# Cing_MainBoard.net
KiCad netlist of a schematic drawn in EAGLE
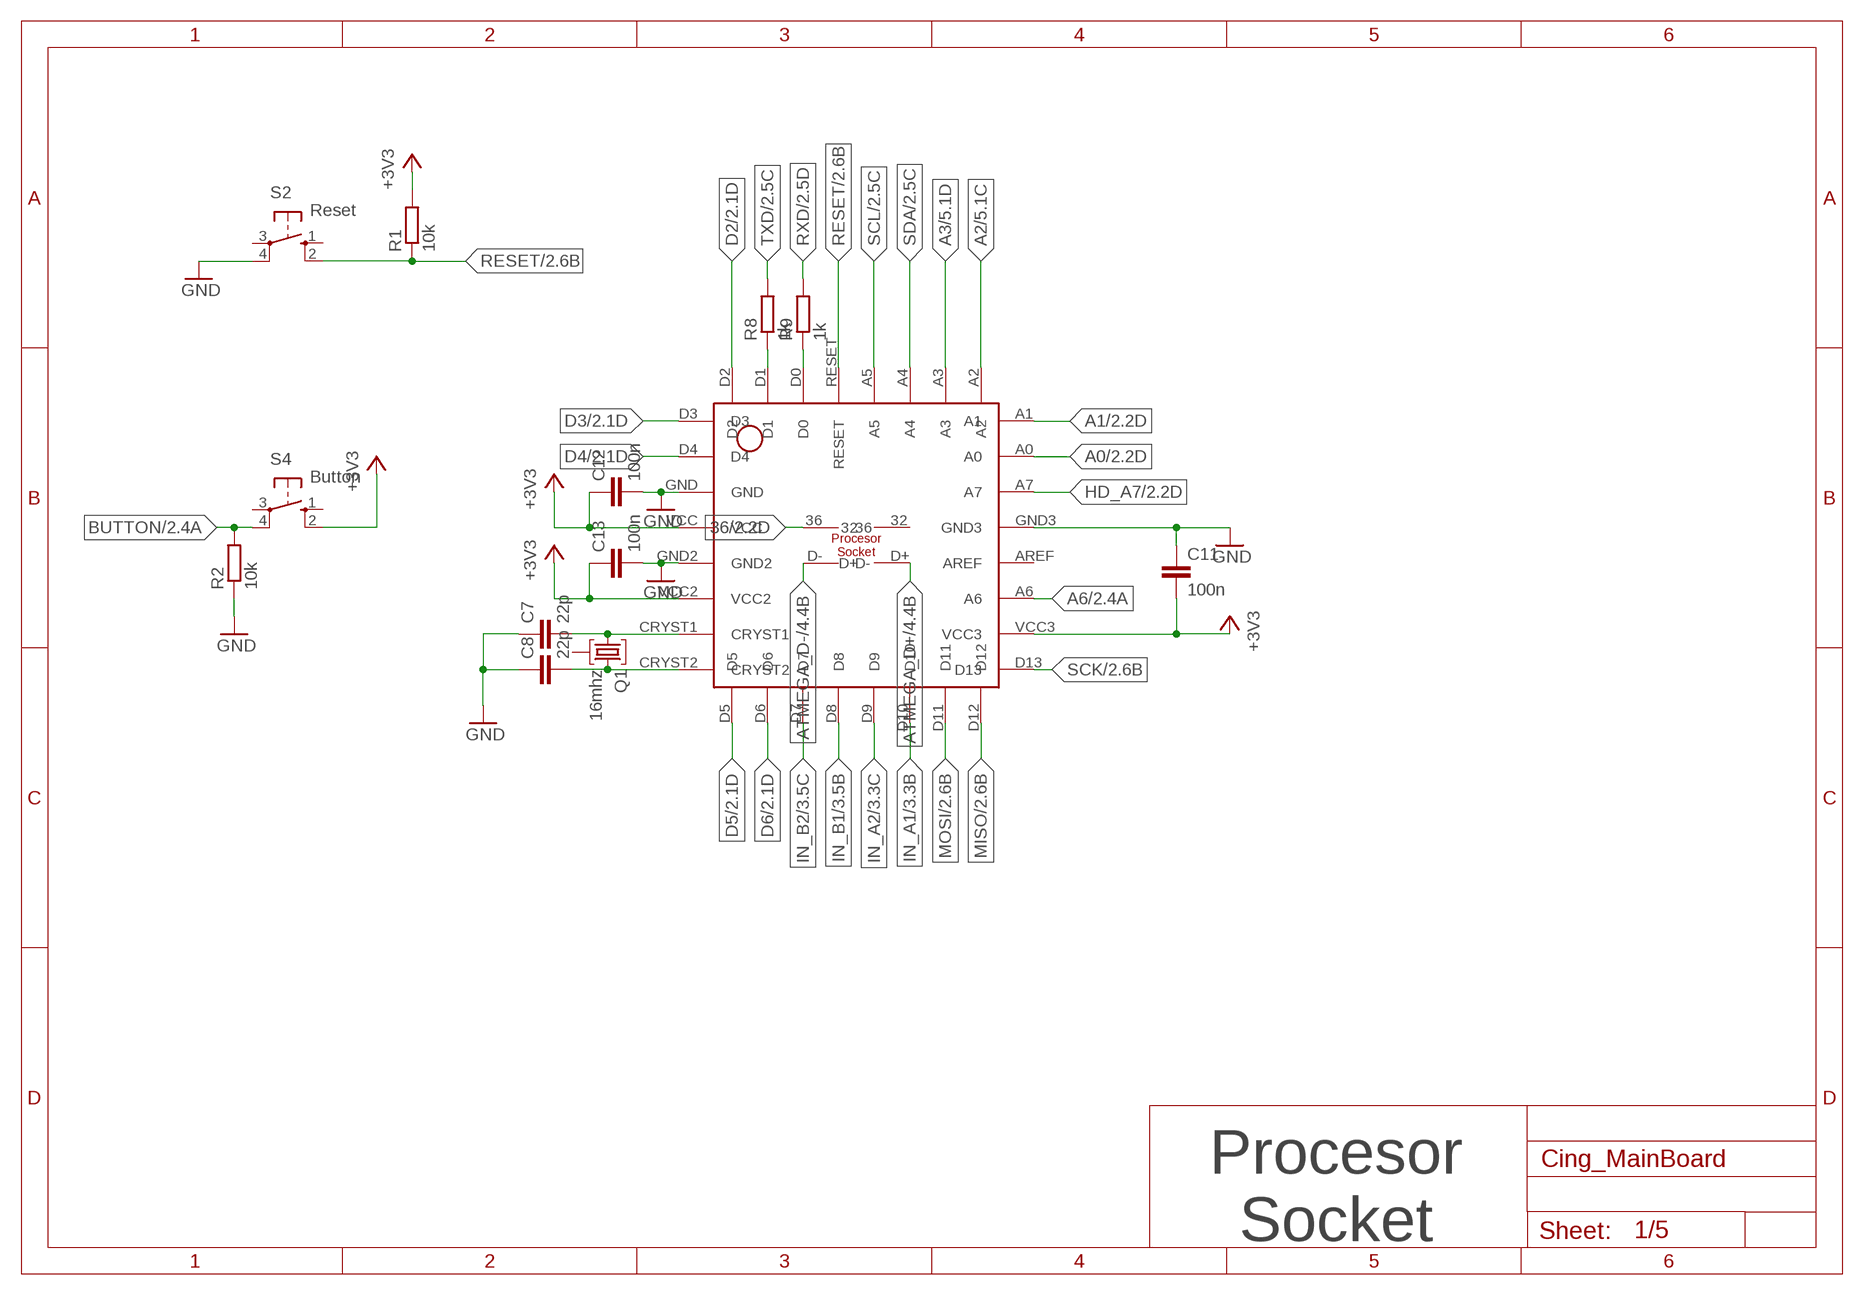
[diagram p0: schematic, sheet 1]
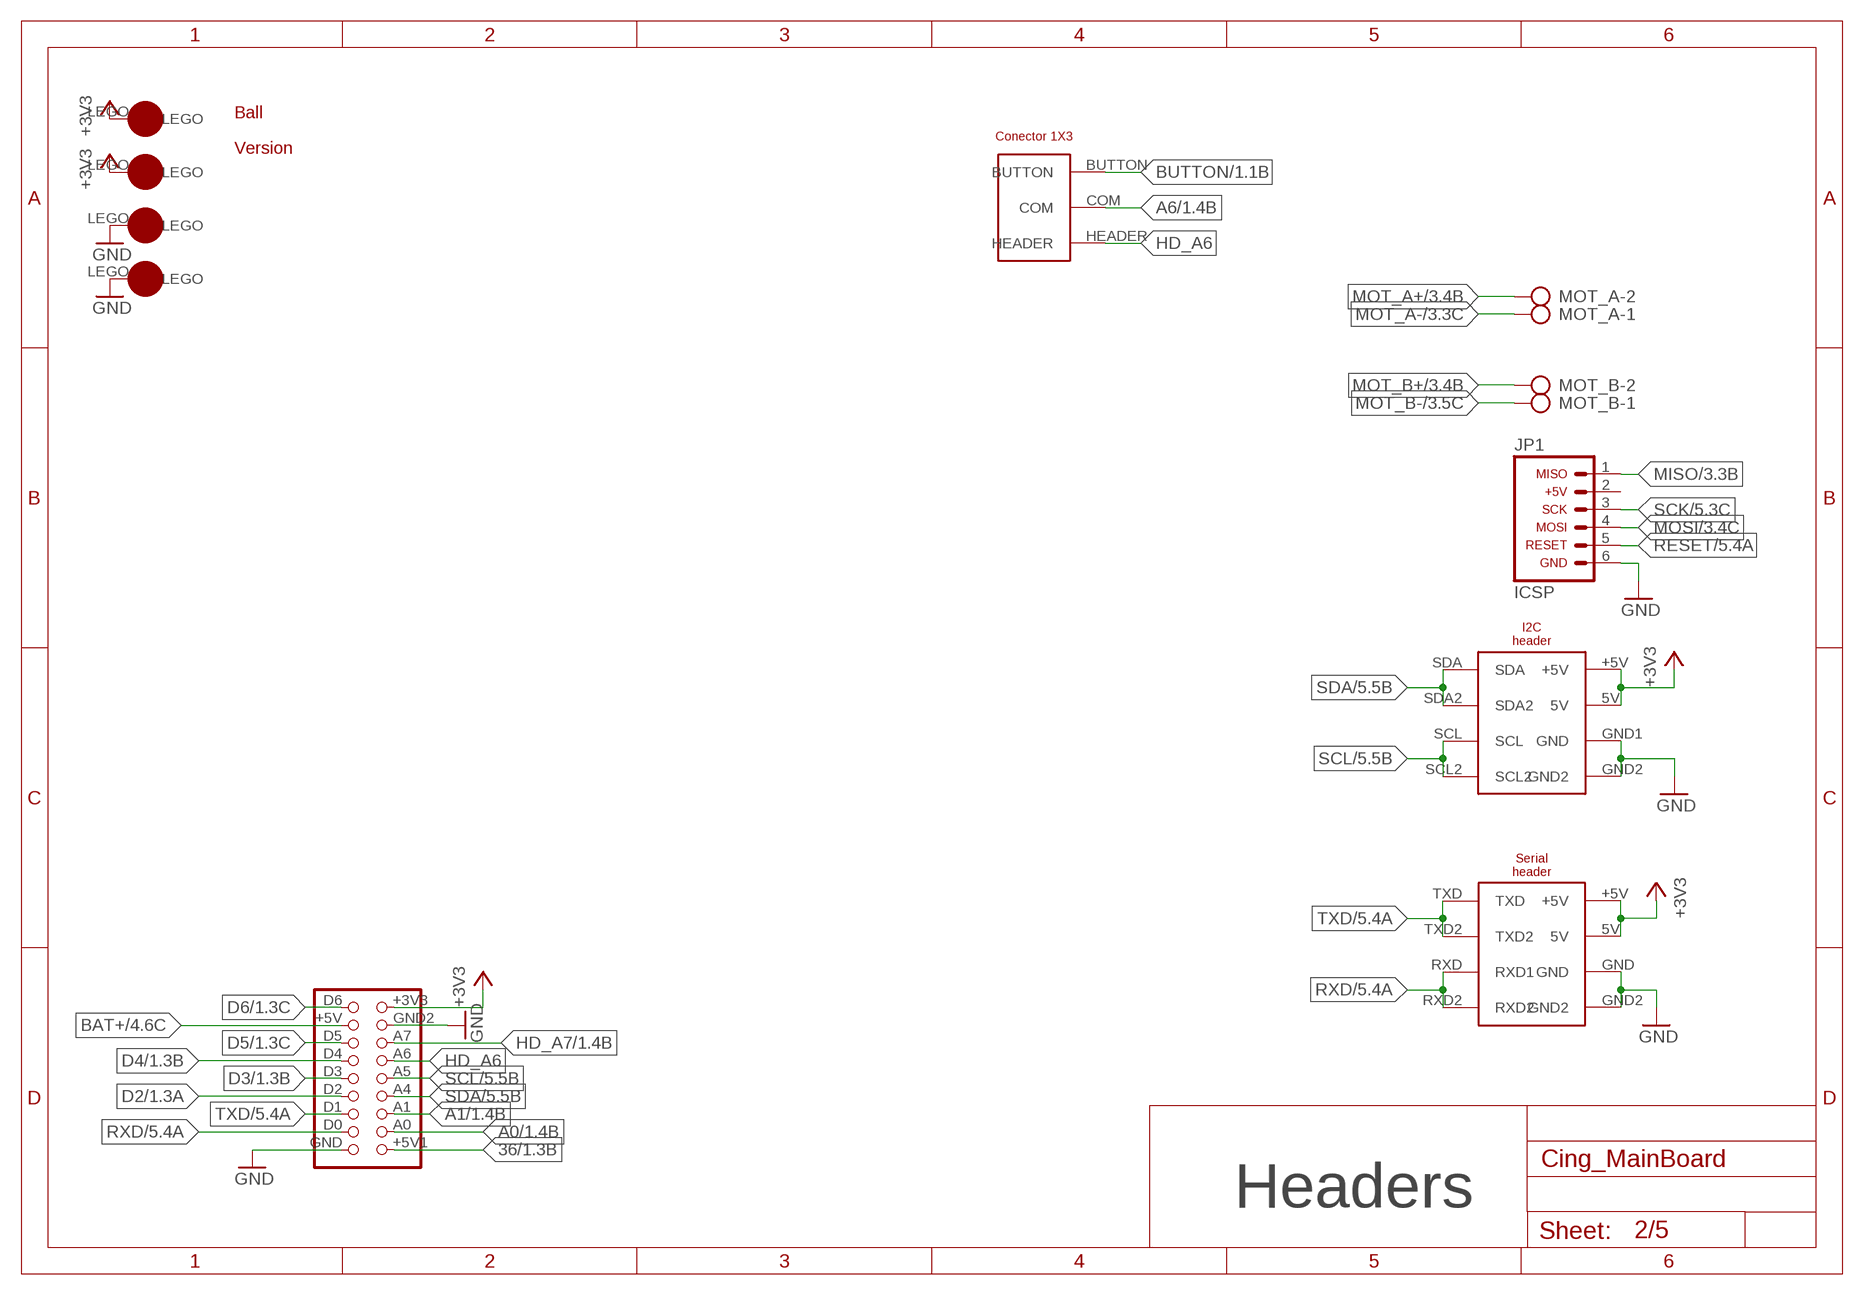
[diagram p1: schematic, sheet 2]
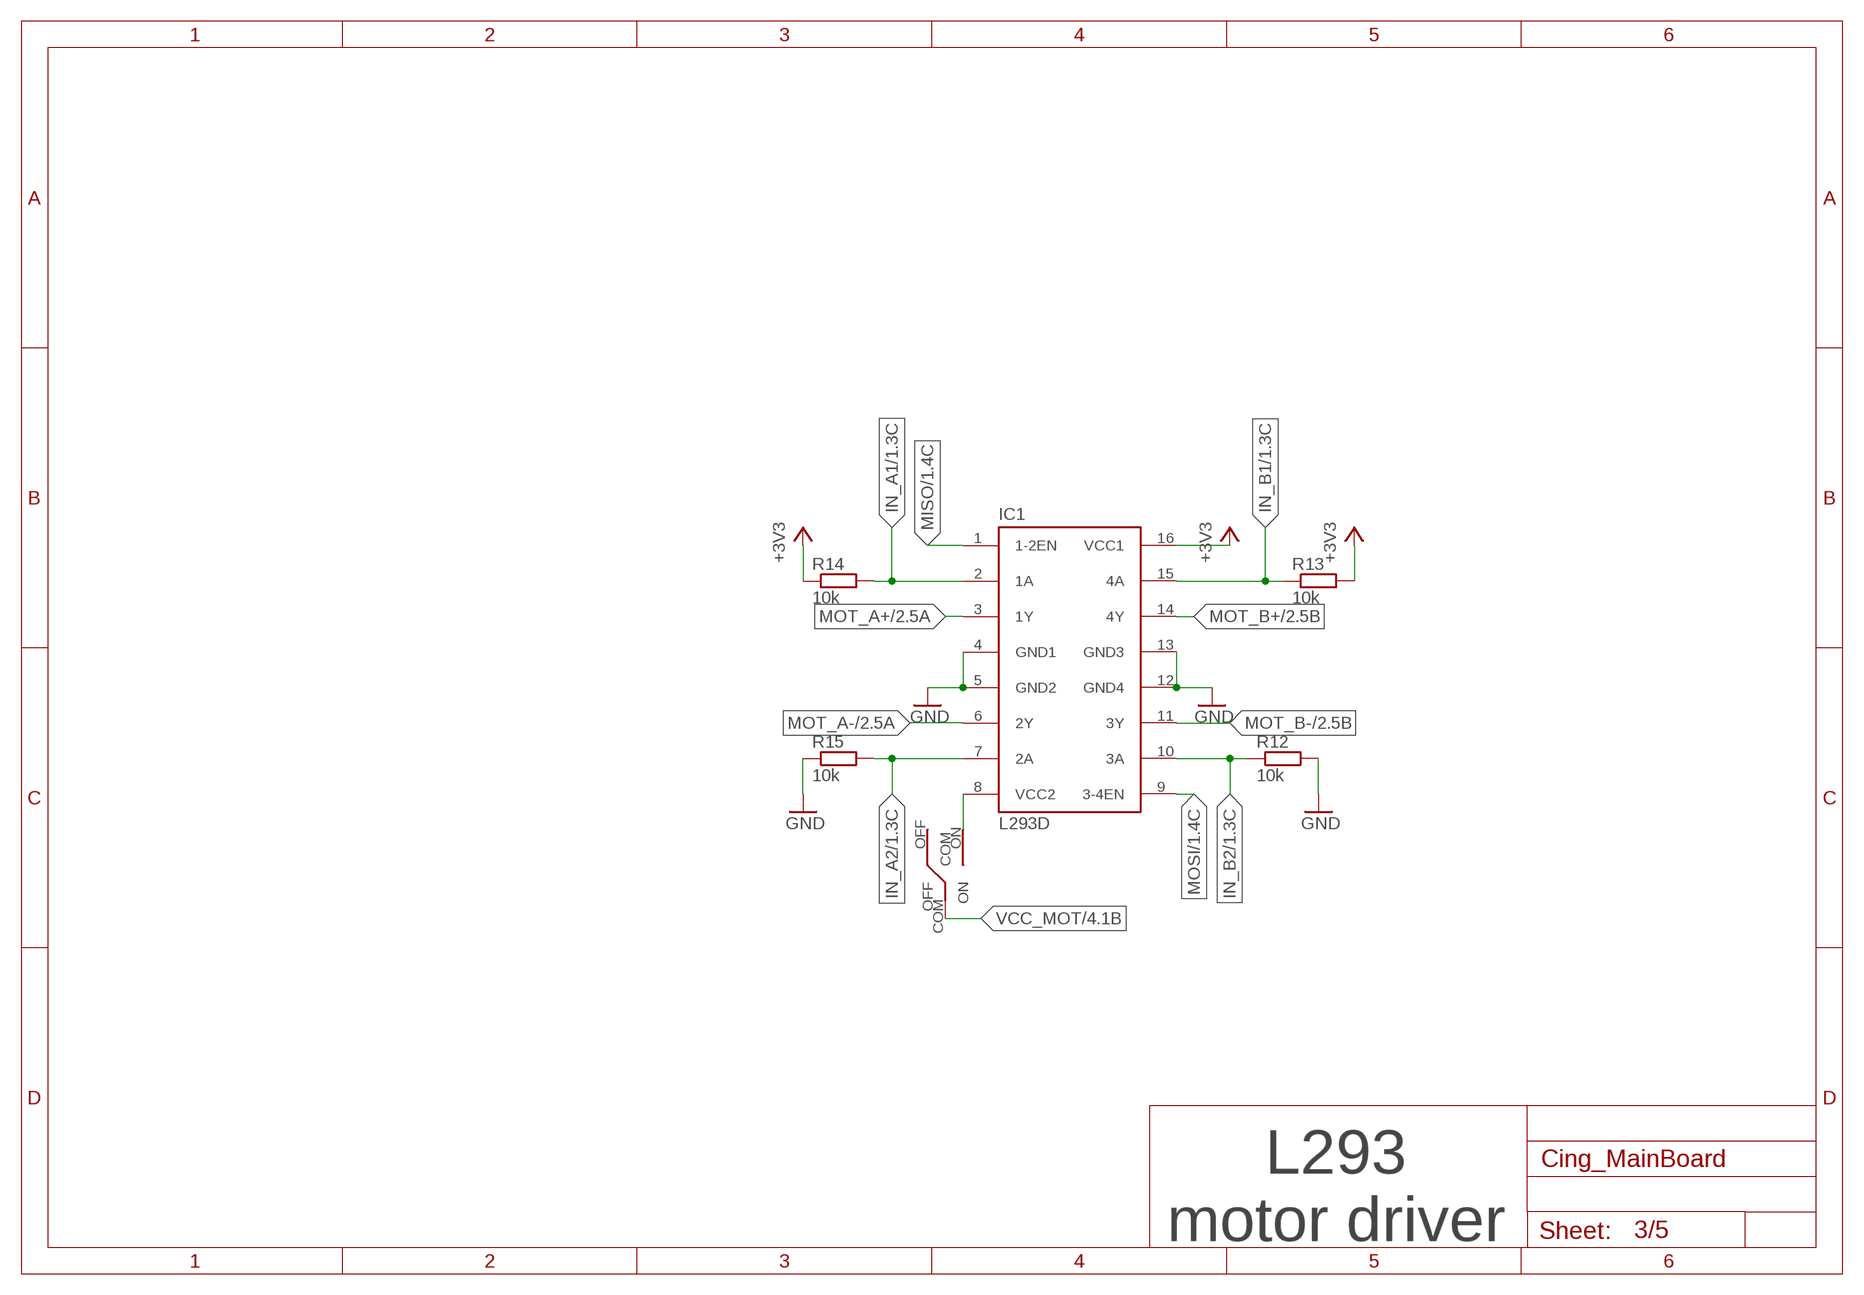
[diagram p2: schematic, sheet 3]
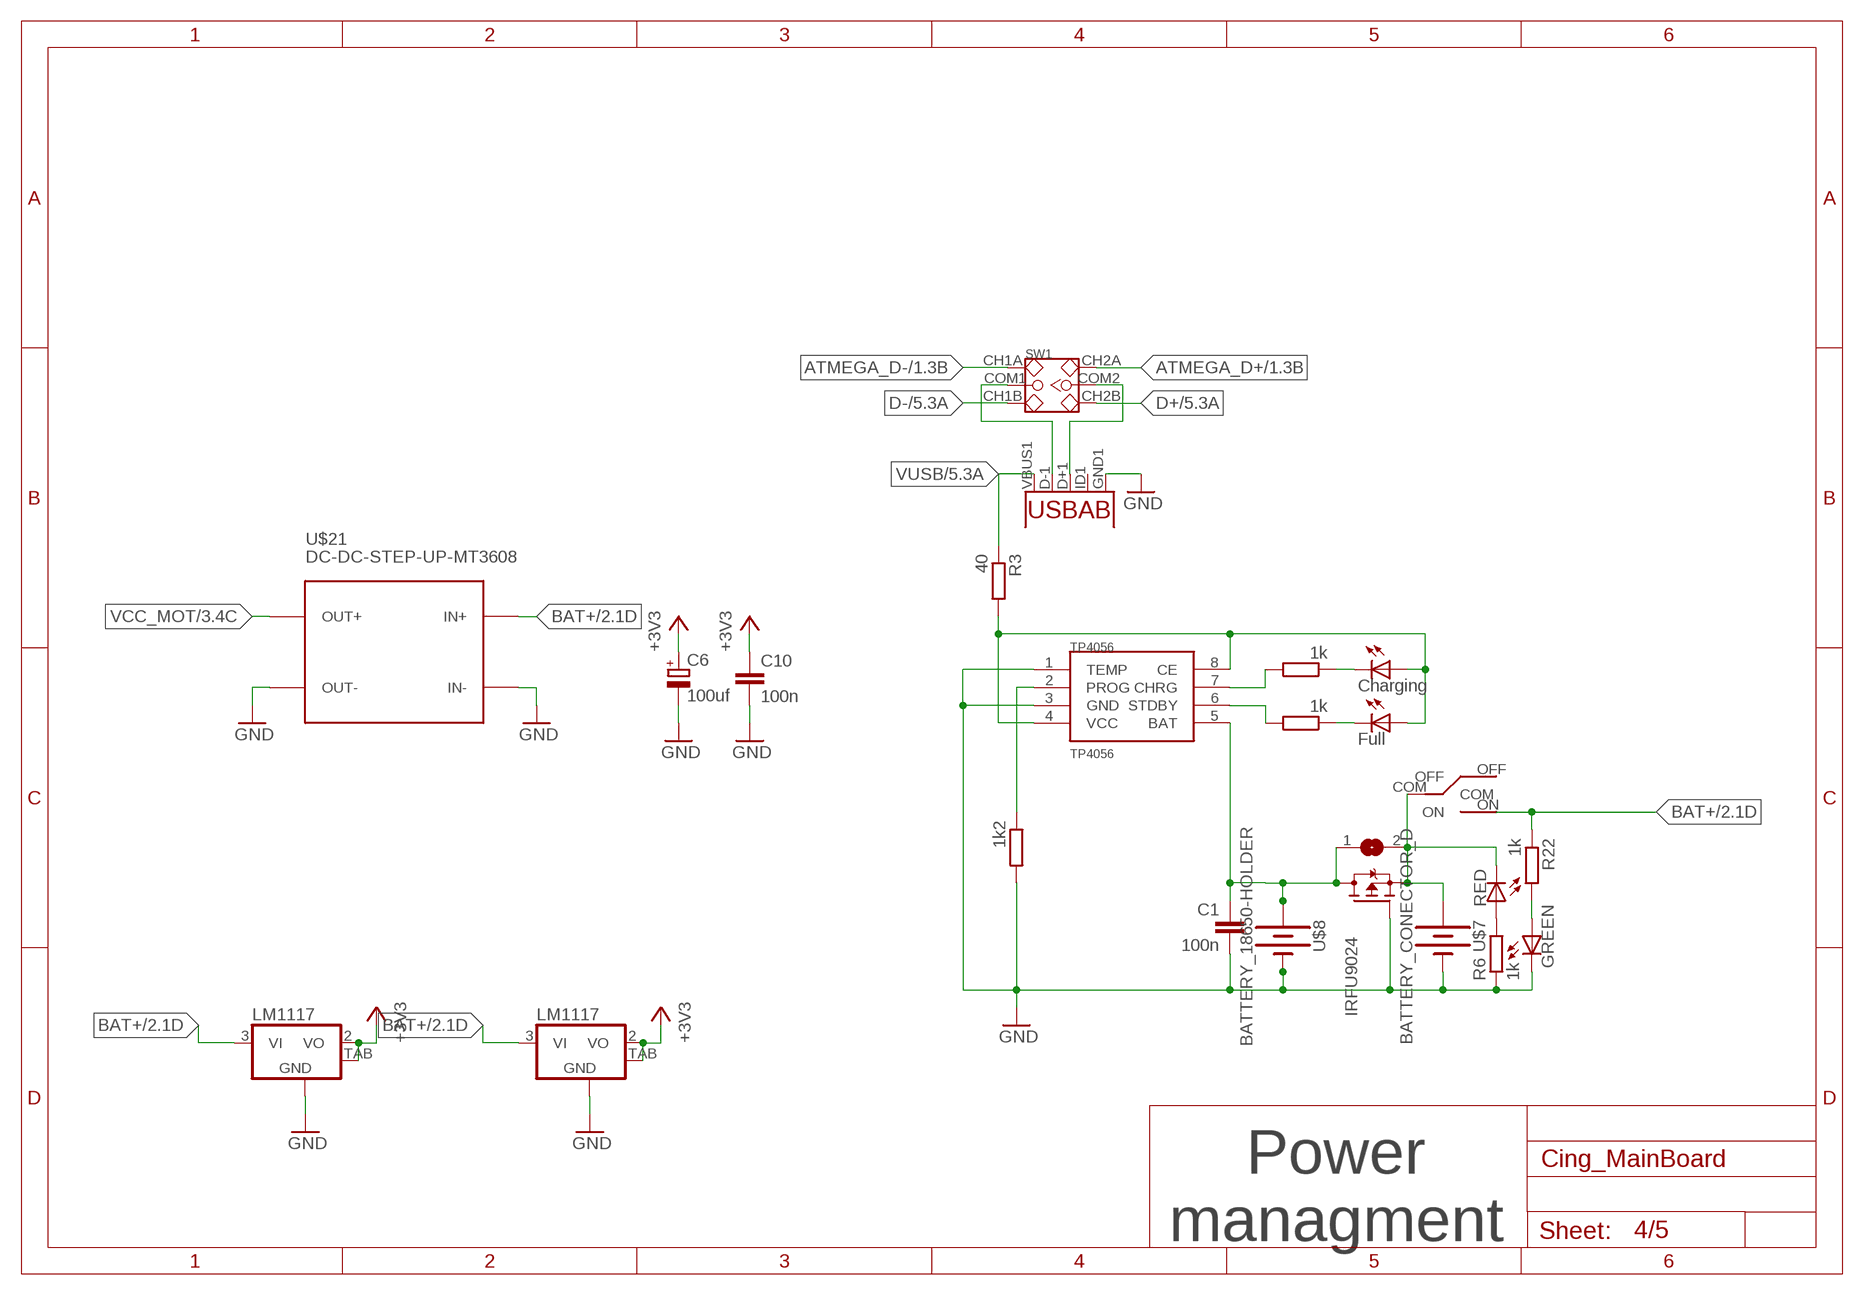
[diagram p3: schematic, sheet 4]
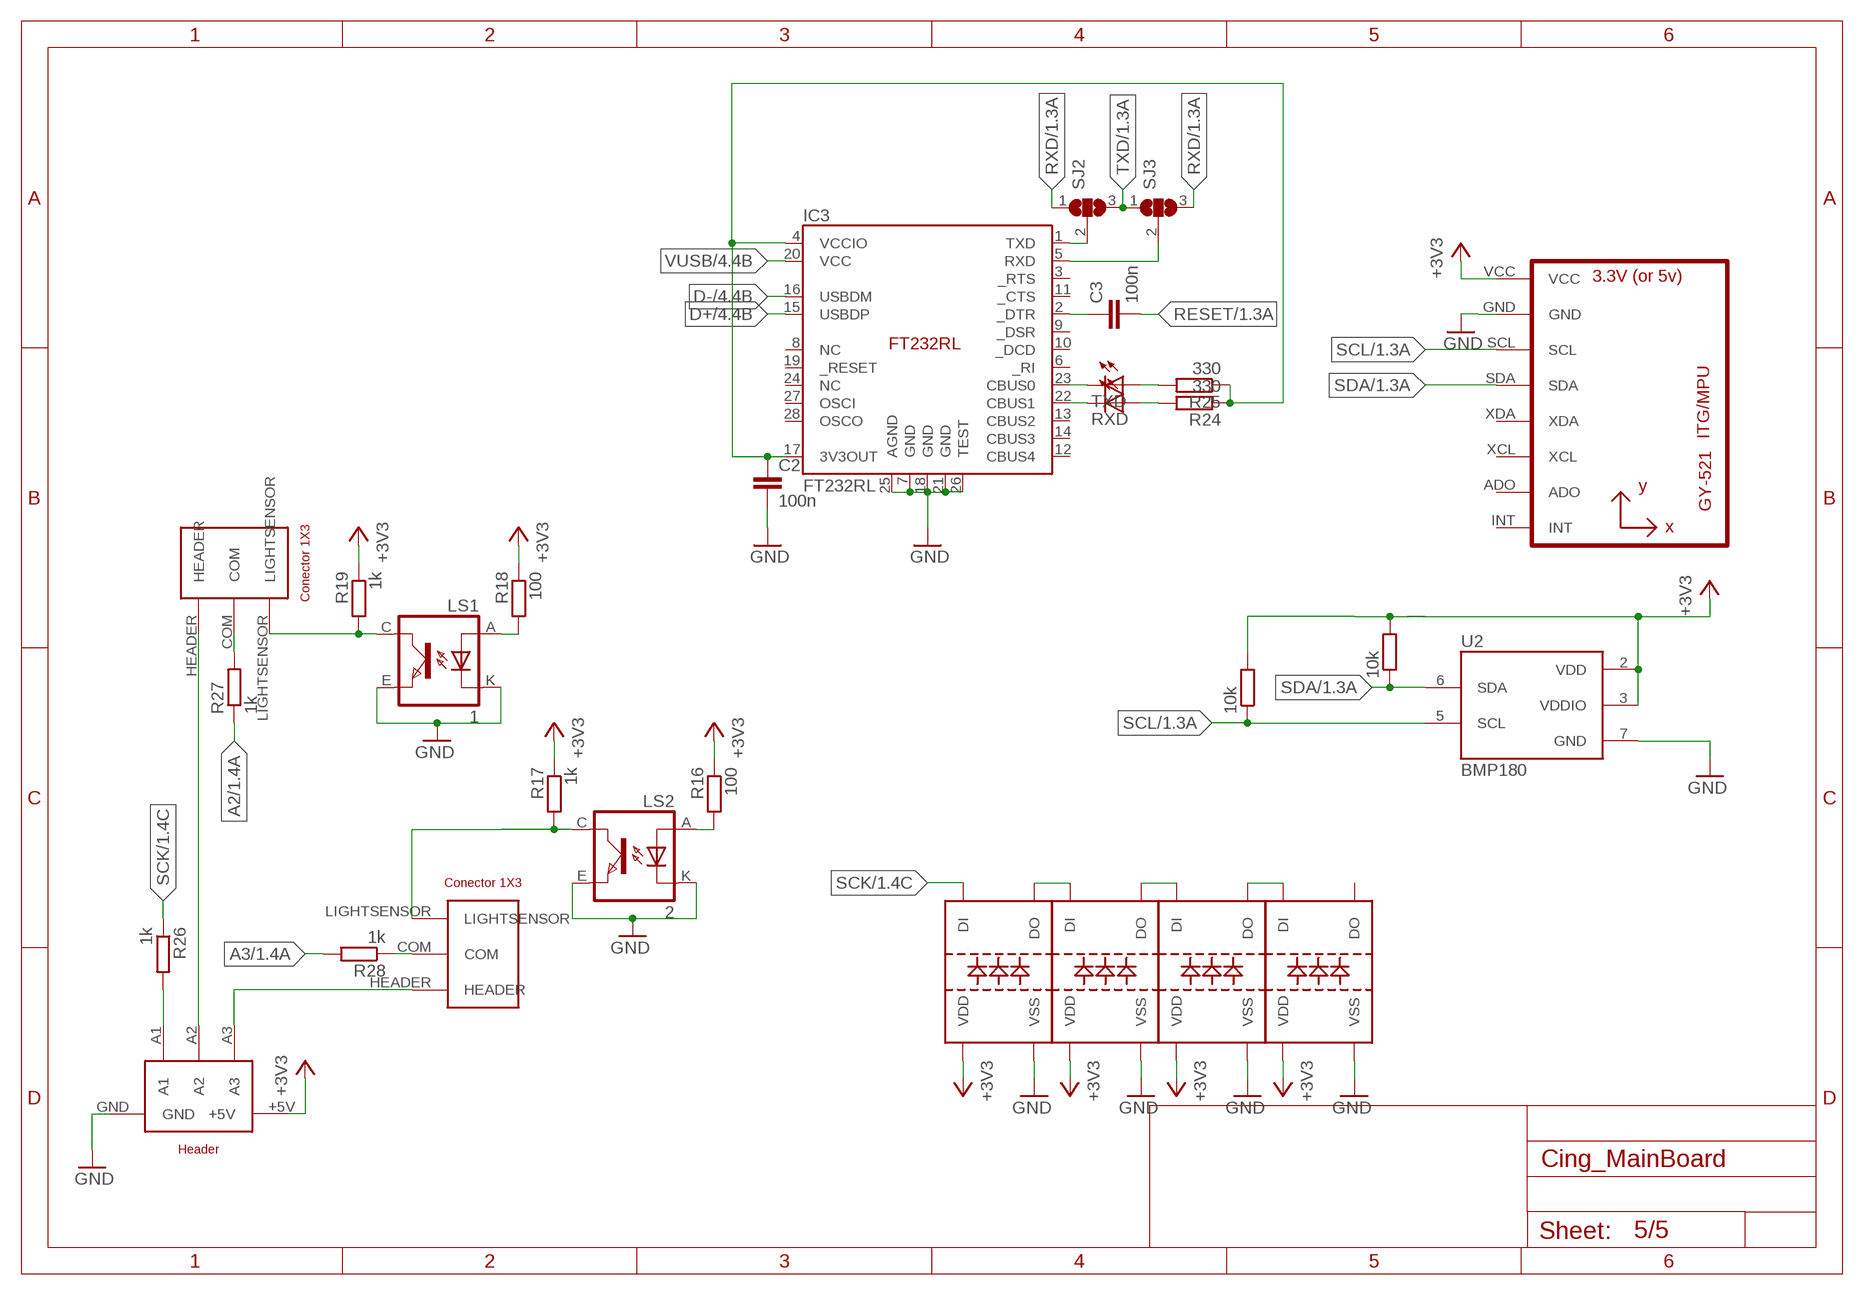
[diagram p4: schematic, sheet 5]

(export (version "E")
  (design (tool "Eeschema 10.0.6"))
  (components
    (comp (ref "C2")
      (value "100n")
      (footprint "eagle-import:C1206")
      (libsource (lib "eagle-import") (part "C-EUC1206"))
    )
    (comp (ref "C3")
      (value "100n")
      (footprint "eagle-import:C1206")
      (libsource (lib "eagle-import") (part "C-EUC1206"))
    )
    (comp (ref "IC3")
      (value "FT232RL")
      (footprint "eagle-import:FT232RL")
      (libsource (lib "eagle-import") (part "FT232RL"))
    )
    (comp (ref "LED3")
      (value "RXD")
      (footprint "eagle-import:1206")
      (libsource (lib "eagle-import") (part "LEDSMT1206"))
    )
    (comp (ref "LED5")
      (value "WS2812B")
      (footprint "eagle-import:WS2812B")
      (libsource (lib "eagle-import") (part "WS2812B"))
    )
    (comp (ref "LED6")
      (value "WS2812B")
      (footprint "eagle-import:WS2812B")
      (libsource (lib "eagle-import") (part "WS2812B"))
    )
    (comp (ref "LED7")
      (value "WS2812B")
      (footprint "eagle-import:WS2812B")
      (libsource (lib "eagle-import") (part "WS2812B"))
    )
    (comp (ref "LED8")
      (value "WS2812B")
      (footprint "eagle-import:WS2812B")
      (libsource (lib "eagle-import") (part "WS2812B"))
    )
    (comp (ref "LS1")
      (value "1")
      (footprint "eagle-import:TCRT5000")
      (libsource (lib "eagle-import") (part "TCRT5000"))
    )
    (comp (ref "LS2")
      (value "2")
      (footprint "eagle-import:TCRT5000")
      (libsource (lib "eagle-import") (part "TCRT5000"))
    )
    (comp (ref "R16")
      (value "100")
      (footprint "eagle-import:R1206")
      (libsource (lib "eagle-import") (part "R-EU_R1206"))
    )
    (comp (ref "R17")
      (value "1k")
      (footprint "eagle-import:R1206")
      (libsource (lib "eagle-import") (part "R-EU_R1206"))
    )
    (comp (ref "R18")
      (value "100")
      (footprint "eagle-import:R1206")
      (libsource (lib "eagle-import") (part "R-EU_R1206"))
    )
    (comp (ref "R19")
      (value "1k")
      (footprint "eagle-import:R1206")
      (libsource (lib "eagle-import") (part "R-EU_R1206"))
    )
    (comp (ref "R24")
      (value "330")
      (footprint "eagle-import:R1206")
      (libsource (lib "eagle-import") (part "R-EU_R1206"))
    )
    (comp (ref "R25")
      (value "330")
      (footprint "eagle-import:R1206")
      (libsource (lib "eagle-import") (part "R-EU_R1206"))
    )
    (comp (ref "R26")
      (value "1k")
      (footprint "eagle-import:R1206")
      (libsource (lib "eagle-import") (part "R-EU_R1206"))
    )
    (comp (ref "R27")
      (value "1k")
      (footprint "eagle-import:R1206")
      (libsource (lib "eagle-import") (part "R-EU_R1206"))
    )
    (comp (ref "R28")
      (value "1k")
      (footprint "eagle-import:R1206")
      (libsource (lib "eagle-import") (part "R-EU_R1206"))
    )
    (comp (ref "R30")
      (value "10k")
      (footprint "eagle-import:R1206")
      (libsource (lib "eagle-import") (part "R-EU_R1206"))
    )
    (comp (ref "R31")
      (value "10k")
      (footprint "eagle-import:R1206")
      (libsource (lib "eagle-import") (part "R-EU_R1206"))
    )
    (comp (ref "SJ2")
      (value "SJ2W")
      (footprint "eagle-import:SJ_2")
      (libsource (lib "eagle-import") (part "SJ2W"))
    )
    (comp (ref "SJ3")
      (value "SJ2W")
      (footprint "eagle-import:SJ_2")
      (libsource (lib "eagle-import") (part "SJ2W"))
    )
    (comp (ref "TXD")
      (value "TXD")
      (footprint "eagle-import:1206")
      (libsource (lib "eagle-import") (part "LEDSMT1206"))
    )
    (comp (ref "U$12")
      (value "CONNECTOR_1X5")
      (footprint "eagle-import:CONNECTOR_1X5")
      (libsource (lib "eagle-import") (part "CONNECTOR_1X5"))
    )
    (comp (ref "U$13")
      (value "CONNECTOR_LIGHT_SENSOR")
      (footprint "eagle-import:CONNECTOR_LIGHT_SENSOR")
      (libsource (lib "eagle-import") (part "CONNECTOR_LIGHT_SENSOR"))
    )
    (comp (ref "U$14")
      (value "CONNECTOR_LIGHT_SENSOR")
      (footprint "eagle-import:CONNECTOR_LIGHT_SENSOR")
      (libsource (lib "eagle-import") (part "CONNECTOR_LIGHT_SENSOR"))
    )
    (comp (ref "U2")
      (value "BMP180")
      (footprint "eagle-import:BMP180")
      (libsource (lib "eagle-import") (part "BMP180"))
    )
    (comp (ref "U3")
      (value "MPU-6050MPU6050")
      (footprint "eagle-import:MPU-6050")
      (libsource (lib "eagle-import") (part "MPU-6050MPU6050"))
    )
    (comp (ref "JP1")
      (value "ICSP")
      (footprint "eagle-import:ICSP_HEADER")
      (libsource (lib "eagle-import") (part "ICSP_HEADER"))
    )
    (comp (ref "MOT_A")
      (value "AK500/2")
      (footprint "eagle-import:AK500_2")
      (libsource (lib "eagle-import") (part "AK500/2"))
    )
    (comp (ref "MOT_B")
      (value "AK500/2")
      (footprint "eagle-import:AK500_2")
      (libsource (lib "eagle-import") (part "AK500/2"))
    )
    (comp (ref "U$2")
      (value "BIG_HEADER")
      (footprint "eagle-import:BIG_HEADER")
      (libsource (lib "eagle-import") (part "BIG_HEADER"))
    )
    (comp (ref "U$3")
      (value "I2C_HEADER")
      (footprint "eagle-import:I2_HEADER")
      (libsource (lib "eagle-import") (part "I2C_HEADER"))
    )
    (comp (ref "U$4")
      (value "SERIAL_HEADER")
      (footprint "eagle-import:SERIAL_HEADER")
      (libsource (lib "eagle-import") (part "SERIAL_HEADER"))
    )
    (comp (ref "U$15")
      (value "CONNECTOR_BUTTON")
      (footprint "eagle-import:CONNECTOR_BUTTON")
      (libsource (lib "eagle-import") (part "CONNECTOR_BUTTON"))
    )
    (comp (ref "U$16")
      (value "3.3V")
      (footprint "eagle-import:LEGO-1X1")
      (libsource (lib "eagle-import") (part "LEGO-1X1"))
    )
    (comp (ref "U$17")
      (value "3.3V")
      (footprint "eagle-import:LEGO-1X1")
      (libsource (lib "eagle-import") (part "LEGO-1X1"))
    )
    (comp (ref "U$18")
      (value "GND")
      (footprint "eagle-import:LEGO-1X1")
      (libsource (lib "eagle-import") (part "LEGO-1X1"))
    )
    (comp (ref "U$19")
      (value "GND")
      (footprint "eagle-import:LEGO-1X1")
      (libsource (lib "eagle-import") (part "LEGO-1X1"))
    )
    (comp (ref "U$20")
      (value "BALL")
      (footprint "eagle-import:BALL")
      (libsource (lib "eagle-import") (part "BALL"))
    )
    (comp (ref "VERSION")
      (value "2.0")
      (footprint "eagle-import:VERSION")
      (libsource (lib "eagle-import") (part "VERSION"))
    )
    (comp (ref "C7")
      (value "22p")
      (footprint "eagle-import:C1206")
      (libsource (lib "eagle-import") (part "C-EUC1206"))
    )
    (comp (ref "C8")
      (value "22p")
      (footprint "eagle-import:C1206")
      (libsource (lib "eagle-import") (part "C-EUC1206"))
    )
    (comp (ref "C11")
      (value "100n")
      (footprint "eagle-import:C1206")
      (libsource (lib "eagle-import") (part "C-EUC1206"))
    )
    (comp (ref "C12")
      (value "100n")
      (footprint "eagle-import:C1206")
      (libsource (lib "eagle-import") (part "C-EUC1206"))
    )
    (comp (ref "C13")
      (value "100n")
      (footprint "eagle-import:C1206")
      (libsource (lib "eagle-import") (part "C-EUC1206"))
    )
    (comp (ref "Q1")
      (value "16mhz")
      (footprint "eagle-import:HC49U")
      (libsource (lib "eagle-import") (part "12M10AHC49HT"))
    )
    (comp (ref "R1")
      (value "10k")
      (footprint "eagle-import:R1206")
      (libsource (lib "eagle-import") (part "R-EU_R1206"))
    )
    (comp (ref "R2")
      (value "10k")
      (footprint "eagle-import:R1206")
      (libsource (lib "eagle-import") (part "R-EU_R1206"))
    )
    (comp (ref "R8")
      (value "1k")
      (footprint "eagle-import:R1206")
      (libsource (lib "eagle-import") (part "R-EU_R1206"))
    )
    (comp (ref "R9")
      (value "1k")
      (footprint "eagle-import:R1206")
      (libsource (lib "eagle-import") (part "R-EU_R1206"))
    )
    (comp (ref "S2")
      (value "Reset")
      (footprint "eagle-import:B3F-10XX")
      (fields (field (name "MPN") "B3F-1000"))
      (libsource (lib "eagle-import") (part "10-XX"))
    )
    (comp (ref "S4")
      (value "Button")
      (footprint "eagle-import:B3F-10XX")
      (fields (field (name "MPN") "B3F-1000"))
      (libsource (lib "eagle-import") (part "10-XX"))
    )
    (comp (ref "U$1")
      (value "PROCESSOR-SOCKET_PCB")
      (footprint "eagle-import:PROCESSOR-SOCKET_PCB")
      (libsource (lib "eagle-import") (part "PROCESSOR-SOCKET_PCB"))
    )
    (comp (ref "IC1")
      (value "L293D")
      (footprint "eagle-import:L293")
      (libsource (lib "eagle-import") (part "L293D"))
    )
    (comp (ref "R12")
      (value "10k")
      (footprint "eagle-import:R1206")
      (libsource (lib "eagle-import") (part "R-EU_R1206"))
    )
    (comp (ref "R13")
      (value "10k")
      (footprint "eagle-import:R1206")
      (libsource (lib "eagle-import") (part "R-EU_R1206"))
    )
    (comp (ref "R14")
      (value "10k")
      (footprint "eagle-import:R1206")
      (libsource (lib "eagle-import") (part "R-EU_R1206"))
    )
    (comp (ref "R15")
      (value "10k")
      (footprint "eagle-import:R1206")
      (libsource (lib "eagle-import") (part "R-EU_R1206"))
    )
    (comp (ref "U$5")
      (value "SWITCH")
      (footprint "eagle-import:SWITCH")
      (libsource (lib "eagle-import") (part "SWITCH"))
    )
    (comp (ref "C1")
      (value "100n")
      (footprint "eagle-import:C1206")
      (libsource (lib "eagle-import") (part "C-EUC1206"))
    )
    (comp (ref "C6")
      (value "100uf")
      (footprint "eagle-import:E3,5-8")
      (libsource (lib "eagle-import") (part "CPOL-EUE3.5-8"))
    )
    (comp (ref "C10")
      (value "100n")
      (footprint "eagle-import:C1206")
      (libsource (lib "eagle-import") (part "C-EUC1206"))
    )
    (comp (ref "IRFU9024")
      (value "IRFU9024")
      (footprint "eagle-import:IRFU9024")
      (libsource (lib "eagle-import") (part "IRFU9024"))
    )
    (comp (ref "LED1")
      (value "Charging")
      (footprint "eagle-import:1206")
      (libsource (lib "eagle-import") (part "LEDSMT1206"))
    )
    (comp (ref "ON")
      (value "GREEN")
      (footprint "eagle-import:1206")
      (libsource (lib "eagle-import") (part "LEDSMT1206"))
    )
    (comp (ref "R3")
      (value "40")
      (footprint "eagle-import:R1206")
      (libsource (lib "eagle-import") (part "R-EU_R1206"))
    )
    (comp (ref "R4")
      (value "1k2")
      (footprint "eagle-import:R1206")
      (libsource (lib "eagle-import") (part "R-EU_R1206"))
    )
    (comp (ref "R5")
      (value "1k")
      (footprint "eagle-import:R1206")
      (libsource (lib "eagle-import") (part "R-EU_R1206"))
    )
    (comp (ref "R6")
      (value "1k")
      (footprint "eagle-import:R1206")
      (libsource (lib "eagle-import") (part "R-EU_R1206"))
    )
    (comp (ref "R11")
      (value "1k")
      (footprint "eagle-import:R1206")
      (libsource (lib "eagle-import") (part "R-EU_R1206"))
    )
    (comp (ref "R22")
      (value "1k")
      (footprint "eagle-import:R1206")
      (libsource (lib "eagle-import") (part "R-EU_R1206"))
    )
    (comp (ref "REVERSE")
      (value "RED")
      (footprint "eagle-import:1206")
      (libsource (lib "eagle-import") (part "LEDSMT1206"))
    )
    (comp (ref "SJ1") (value "SJ") (footprint "eagle-import:SJ") (libsource (lib "eagle-import") (part "SJ")))
    (comp (ref "SW1")
      (value "USB_SWITCH")
      (footprint "eagle-import:USB_SWITCH")
      (libsource (lib "eagle-import") (part "USB_SWITCH"))
    )
    (comp (ref "TP4056")
      (value "TP4056")
      (footprint "eagle-import:TP4056")
      (libsource (lib "eagle-import") (part "TP4056"))
    )
    (comp (ref "U$7")
      (value "BATTERY_CONECTOR_D")
      (footprint "eagle-import:BATTERY_CONECTOR_D")
      (libsource (lib "eagle-import") (part "BATTERY_CONECTOR_D"))
    )
    (comp (ref "U$8")
      (value "BATTERY_18650-HOLDER")
      (footprint "eagle-import:BATTERY_18650-HOLDER")
      (libsource (lib "eagle-import") (part "BATTERY_18650-HOLDER"))
    )
    (comp (ref "U$9")
      (value "SWITCH")
      (footprint "eagle-import:SWITCH")
      (libsource (lib "eagle-import") (part "SWITCH"))
    )
    (comp (ref "U$10")
      (value "LM1117")
      (footprint "eagle-import:LM1117")
      (libsource (lib "eagle-import") (part "LM1117"))
    )
    (comp (ref "U$11")
      (value "LM1117")
      (footprint "eagle-import:LM1117")
      (libsource (lib "eagle-import") (part "LM1117"))
    )
    (comp (ref "U$21")
      (value "DC-DC-STEP-UP-MT3608")
      (footprint "eagle-import:DC-DC-STEP-UP-MT3608")
      (libsource (lib "eagle-import") (part "DC-DC-STEP-UP-MT3608"))
    )
    (comp (ref "U1")
      (value "MICRO_USB\"\"")
      (footprint "eagle-import:USB-MICRO-SMD")
      (libsource (lib "eagle-import") (part "MICRO_USB{dblquote}{dblquote}"))
    )
    (comp (ref "YELLOW")
      (value "Full")
      (footprint "eagle-import:1206")
      (libsource (lib "eagle-import") (part "LEDSMT1206"))
    )
  )
  (nets
    (net (code "1") (name "+3V3") (class "Default")
      (node (ref "C10") (pin "1") (pinfunction "1_1") (pintype "passive"))
      (node (ref "C11") (pin "2") (pinfunction "2_2") (pintype "passive"))
      (node (ref "C12") (pin "1") (pinfunction "1_1") (pintype "passive"))
      (node (ref "C13") (pin "1") (pinfunction "1_1") (pintype "passive"))
      (node (ref "C6") (pin "+") (pinfunction "+_+") (pintype "passive"))
      (node (ref "IC1") (pin "16") (pinfunction "VCC1_16") (pintype "power_in"))
      (node (ref "LED5") (pin "1") (pinfunction "VDD_1") (pintype "bidirectional"))
      (node (ref "LED6") (pin "1") (pinfunction "VDD_1") (pintype "bidirectional"))
      (node (ref "LED7") (pin "1") (pinfunction "VDD_1") (pintype "bidirectional"))
      (node (ref "LED8") (pin "1") (pinfunction "VDD_1") (pintype "bidirectional"))
      (node (ref "R1") (pin "2") (pinfunction "2_2") (pintype "passive"))
      (node (ref "R13") (pin "2") (pinfunction "2_2") (pintype "passive"))
      (node (ref "R14") (pin "1") (pinfunction "1_1") (pintype "passive"))
      (node (ref "R16") (pin "1") (pinfunction "1_1") (pintype "passive"))
      (node (ref "R17") (pin "1") (pinfunction "1_1") (pintype "passive"))
      (node (ref "R18") (pin "1") (pinfunction "1_1") (pintype "passive"))
      (node (ref "R19") (pin "1") (pinfunction "1_1") (pintype "passive"))
      (node (ref "R30") (pin "2") (pinfunction "2_2") (pintype "passive"))
      (node (ref "R31") (pin "2") (pinfunction "2_2") (pintype "passive"))
      (node (ref "S4") (pin "2") (pinfunction "S1_2") (pintype "passive"))
      (node (ref "U$1") (pin "VCC") (pinfunction "VCC_VCC") (pintype "bidirectional"))
      (node (ref "U$1") (pin "VCC2") (pinfunction "VCC2_VCC2") (pintype "bidirectional"))
      (node (ref "U$1") (pin "VCC3") (pinfunction "VCC3_VCC3") (pintype "bidirectional"))
      (node (ref "U$10") (pin "2") (pinfunction "VO_2") (pintype "passive"))
      (node (ref "U$10") (pin "TAB") (pinfunction "OUT_TAB") (pintype "passive"))
      (node (ref "U$11") (pin "2") (pinfunction "VO_2") (pintype "passive"))
      (node (ref "U$11") (pin "TAB") (pinfunction "OUT_TAB") (pintype "passive"))
      (node (ref "U$12") (pin "+5V") (pinfunction "+5V_+5V") (pintype "bidirectional"))
      (node (ref "U$16") (pin "LEGO") (pinfunction "LEGO_LEGO") (pintype "bidirectional"))
      (node (ref "U$17") (pin "LEGO") (pinfunction "LEGO_LEGO") (pintype "bidirectional"))
      (node (ref "U$2") (pin "+3V3") (pinfunction "+3V3_+3V3") (pintype "passive"))
      (node (ref "U$3") (pin "+5V") (pinfunction "+5V_+5V") (pintype "bidirectional"))
      (node (ref "U$3") (pin "5V") (pinfunction "5V_5V") (pintype "bidirectional"))
      (node (ref "U$4") (pin "+5V") (pinfunction "+5V_+5V") (pintype "bidirectional"))
      (node (ref "U$4") (pin "5V") (pinfunction "5V_5V") (pintype "bidirectional"))
      (node (ref "U2") (pin "2") (pinfunction "VDD_2") (pintype "power_in"))
      (node (ref "U2") (pin "3") (pinfunction "VDDIO_3") (pintype "power_in"))
      (node (ref "U3") (pin "VCC") (pinfunction "VCC_VCC") (pintype "bidirectional"))
    )
    (net (code "2") (name "36") (class "Default")
      (node (ref "U$1") (pin "36") (pinfunction "36_36") (pintype "bidirectional"))
      (node (ref "U$2") (pin "+5V1") (pinfunction "+5V1_+5V1") (pintype "passive"))
    )
    (net (code "3") (name "A0") (class "Default")
      (node (ref "U$1") (pin "A0") (pinfunction "A0_A0") (pintype "bidirectional"))
      (node (ref "U$2") (pin "A0") (pinfunction "A0_A0") (pintype "passive"))
    )
    (net (code "4") (name "A1") (class "Default")
      (node (ref "U$1") (pin "A1") (pinfunction "A1_A1") (pintype "bidirectional"))
      (node (ref "U$2") (pin "A1") (pinfunction "A1_A1") (pintype "passive"))
    )
    (net (code "5") (name "A2") (class "Default")
      (node (ref "R27") (pin "1") (pinfunction "1_1") (pintype "passive"))
      (node (ref "U$1") (pin "A2") (pinfunction "A2_A2") (pintype "bidirectional"))
    )
    (net (code "6") (name "A3") (class "Default")
      (node (ref "R28") (pin "2") (pinfunction "2_2") (pintype "passive"))
      (node (ref "U$1") (pin "A3") (pinfunction "A3_A3") (pintype "bidirectional"))
    )
    (net (code "7") (name "A6") (class "Default")
      (node (ref "U$1") (pin "A6") (pinfunction "A6_A6") (pintype "bidirectional"))
      (node (ref "U$15") (pin "COM") (pinfunction "COM_COM") (pintype "bidirectional"))
    )
    (net (code "8") (name "ATMEGA_D+") (class "Default")
      (node (ref "SW1") (pin "CH2A") (pinfunction "CH2A_CH2A") (pintype "bidirectional"))
      (node (ref "U$1") (pin "D+") (pinfunction "D+_D+") (pintype "bidirectional"))
    )
    (net (code "9") (name "ATMEGA_D-") (class "Default")
      (node (ref "SW1") (pin "CH1A") (pinfunction "CH1A_CH1A") (pintype "bidirectional"))
      (node (ref "U$1") (pin "D-") (pinfunction "D-_D-") (pintype "bidirectional"))
    )
    (net (code "10") (name "BAT+") (class "Default")
      (node (ref "R22") (pin "1") (pinfunction "1_1") (pintype "passive"))
      (node (ref "U$10") (pin "3") (pinfunction "VI_3") (pintype "input"))
      (node (ref "U$11") (pin "3") (pinfunction "VI_3") (pintype "input"))
      (node (ref "U$2") (pin "+5V") (pinfunction "+5V_+5V") (pintype "passive"))
      (node (ref "U$21") (pin "IN+") (pinfunction "IN+_IN+") (pintype "bidirectional"))
      (node (ref "U$9") (pin "ON") (pinfunction "ON_ON") (pintype "bidirectional"))
    )
    (net (code "11") (name "BUTTON") (class "Default")
      (node (ref "R2") (pin "2") (pinfunction "2_2") (pintype "passive"))
      (node (ref "S4") (pin "4") (pinfunction "P1_4") (pintype "passive"))
      (node (ref "U$15") (pin "BUTTON") (pinfunction "BUTTON_BUTTON") (pintype "bidirectional"))
    )
    (net (code "12") (name "D+") (class "Default")
      (node (ref "IC3") (pin "15") (pinfunction "USBDP_15") (pintype "bidirectional"))
      (node (ref "SW1") (pin "CH2B") (pinfunction "CH2B_CH2B") (pintype "bidirectional"))
    )
    (net (code "13") (name "D-") (class "Default")
      (node (ref "IC3") (pin "16") (pinfunction "USBDM_16") (pintype "bidirectional"))
      (node (ref "SW1") (pin "CH1B") (pinfunction "CH1B_CH1B") (pintype "bidirectional"))
    )
    (net (code "14") (name "D2") (class "Default")
      (node (ref "U$1") (pin "D2") (pinfunction "D2_D2") (pintype "bidirectional"))
      (node (ref "U$2") (pin "D2") (pinfunction "D2_D2") (pintype "passive"))
    )
    (net (code "15") (name "D3") (class "Default")
      (node (ref "U$1") (pin "D3") (pinfunction "D3_D3") (pintype "bidirectional"))
      (node (ref "U$2") (pin "D3") (pinfunction "D3_D3") (pintype "passive"))
    )
    (net (code "16") (name "D4") (class "Default")
      (node (ref "U$1") (pin "D4") (pinfunction "D4_D4") (pintype "bidirectional"))
      (node (ref "U$2") (pin "D4") (pinfunction "D4_D4") (pintype "passive"))
    )
    (net (code "17") (name "D5") (class "Default")
      (node (ref "U$1") (pin "D5") (pinfunction "D5_D5") (pintype "bidirectional"))
      (node (ref "U$2") (pin "D5") (pinfunction "D5_D5") (pintype "passive"))
    )
    (net (code "18") (name "D6") (class "Default")
      (node (ref "U$1") (pin "D6") (pinfunction "D6_D6") (pintype "bidirectional"))
      (node (ref "U$2") (pin "D6") (pinfunction "D6_D6") (pintype "passive"))
    )
    (net (code "19") (name "GND") (class "Default")
      (node (ref "C1") (pin "2") (pinfunction "2_2") (pintype "passive"))
      (node (ref "C10") (pin "2") (pinfunction "2_2") (pintype "passive"))
      (node (ref "C11") (pin "1") (pinfunction "1_1") (pintype "passive"))
      (node (ref "C12") (pin "2") (pinfunction "2_2") (pintype "passive"))
      (node (ref "C13") (pin "2") (pinfunction "2_2") (pintype "passive"))
      (node (ref "C2") (pin "2") (pinfunction "2_2") (pintype "passive"))
      (node (ref "C6") (pin "-") (pinfunction "-_-") (pintype "passive"))
      (node (ref "C7") (pin "1") (pinfunction "1_1") (pintype "passive"))
      (node (ref "C8") (pin "1") (pinfunction "1_1") (pintype "passive"))
      (node (ref "IC1") (pin "12") (pinfunction "GND4_12") (pintype "power_in"))
      (node (ref "IC1") (pin "13") (pinfunction "GND3_13") (pintype "power_in"))
      (node (ref "IC1") (pin "4") (pinfunction "GND1_4") (pintype "power_in"))
      (node (ref "IC1") (pin "5") (pinfunction "GND2_5") (pintype "power_in"))
      (node (ref "IC3") (pin "18") (pinfunction "GND_18") (pintype "power_in"))
      (node (ref "IC3") (pin "21") (pinfunction "GND_21") (pintype "power_in"))
      (node (ref "IC3") (pin "25") (pinfunction "AGND_25") (pintype "power_in"))
      (node (ref "IC3") (pin "26") (pinfunction "TEST_26") (pintype "bidirectional"))
      (node (ref "IC3") (pin "7") (pinfunction "GND_7") (pintype "power_in"))
      (node (ref "IRFU9024") (pin "G") (pinfunction "G_G") (pintype "passive"))
      (node (ref "JP1") (pin "6") (pinfunction "6_6") (pintype "passive"))
      (node (ref "LED5") (pin "3") (pinfunction "VSS_3") (pintype "bidirectional"))
      (node (ref "LED6") (pin "3") (pinfunction "VSS_3") (pintype "bidirectional"))
      (node (ref "LED7") (pin "3") (pinfunction "VSS_3") (pintype "bidirectional"))
      (node (ref "LED8") (pin "3") (pinfunction "VSS_3") (pintype "bidirectional"))
      (node (ref "LS1") (pin "E") (pinfunction "EMITTER_E") (pintype "passive"))
      (node (ref "LS1") (pin "K") (pinfunction "CATHODE_K") (pintype "passive"))
      (node (ref "LS2") (pin "E") (pinfunction "EMITTER_E") (pintype "passive"))
      (node (ref "LS2") (pin "K") (pinfunction "CATHODE_K") (pintype "passive"))
      (node (ref "ON") (pin "C") (pinfunction "C_C") (pintype "passive"))
      (node (ref "R12") (pin "2") (pinfunction "2_2") (pintype "passive"))
      (node (ref "R15") (pin "1") (pinfunction "1_1") (pintype "passive"))
      (node (ref "R2") (pin "1") (pinfunction "1_1") (pintype "passive"))
      (node (ref "R4") (pin "2") (pinfunction "2_2") (pintype "passive"))
      (node (ref "R6") (pin "1") (pinfunction "1_1") (pintype "passive"))
      (node (ref "S2") (pin "4") (pinfunction "P1_4") (pintype "passive"))
      (node (ref "TP4056") (pin "1") (pinfunction "TEMP_1") (pintype "bidirectional"))
      (node (ref "TP4056") (pin "3") (pinfunction "GND_3") (pintype "bidirectional"))
      (node (ref "U$1") (pin "GND") (pinfunction "GND_GND") (pintype "bidirectional"))
      (node (ref "U$1") (pin "GND2") (pinfunction "GND2_GND2") (pintype "bidirectional"))
      (node (ref "U$1") (pin "GND3") (pinfunction "GND3_GND3") (pintype "bidirectional"))
      (node (ref "U$10") (pin "1") (pinfunction "GND_1") (pintype "passive"))
      (node (ref "U$11") (pin "1") (pinfunction "GND_1") (pintype "passive"))
      (node (ref "U$12") (pin "GND") (pinfunction "GND_GND") (pintype "bidirectional"))
      (node (ref "U$18") (pin "LEGO") (pinfunction "LEGO_LEGO") (pintype "bidirectional"))
      (node (ref "U$19") (pin "LEGO") (pinfunction "LEGO_LEGO") (pintype "bidirectional"))
      (node (ref "U$2") (pin "GND") (pinfunction "GND_GND") (pintype "passive"))
      (node (ref "U$2") (pin "GND2") (pinfunction "GND1_GND2") (pintype "passive"))
      (node (ref "U$21") (pin "IN-") (pinfunction "IN-_IN-") (pintype "bidirectional"))
      (node (ref "U$21") (pin "OUT-") (pinfunction "OUT-_OUT-") (pintype "bidirectional"))
      (node (ref "U$3") (pin "GND1") (pinfunction "GND_GND1") (pintype "bidirectional"))
      (node (ref "U$3") (pin "GND2") (pinfunction "GND2_GND2") (pintype "bidirectional"))
      (node (ref "U$4") (pin "GND") (pinfunction "GND_GND") (pintype "bidirectional"))
      (node (ref "U$4") (pin "GND2") (pinfunction "GND2_GND2") (pintype "bidirectional"))
      (node (ref "U$7") (pin "-") (pinfunction "-_-") (pintype "power_in"))
      (node (ref "U$8") (pin "GND@1") (pinfunction "-_GND@1") (pintype "power_in"))
      (node (ref "U$8") (pin "GND@2") (pinfunction "-1_GND@2") (pintype "power_in"))
      (node (ref "U$8") (pin "GND@3") (pinfunction "-2_GND@3") (pintype "power_in"))
      (node (ref "U1") (pin "GND1") (pinfunction "GND_GND1") (pintype "bidirectional"))
      (node (ref "U2") (pin "7") (pinfunction "GND_7") (pintype "power_in"))
      (node (ref "U3") (pin "GND") (pinfunction "GND_GND") (pintype "bidirectional"))
    )
    (net (code "20") (name "HD_A6") (class "Default")
      (node (ref "U$15") (pin "HEADER") (pinfunction "HEADER_HEADER") (pintype "bidirectional"))
      (node (ref "U$2") (pin "A6") (pinfunction "A6_A6") (pintype "passive"))
    )
    (net (code "21") (name "HD_A7") (class "Default")
      (node (ref "U$1") (pin "A7") (pinfunction "A7_A7") (pintype "bidirectional"))
      (node (ref "U$2") (pin "A7") (pinfunction "A7_A7") (pintype "passive"))
    )
    (net (code "22") (name "IN_A1") (class "Default")
      (node (ref "IC1") (pin "2") (pinfunction "1A_2") (pintype "input"))
      (node (ref "R14") (pin "2") (pinfunction "2_2") (pintype "passive"))
      (node (ref "U$1") (pin "D10") (pinfunction "D10_D10") (pintype "bidirectional"))
    )
    (net (code "23") (name "IN_A2") (class "Default")
      (node (ref "IC1") (pin "7") (pinfunction "2A_7") (pintype "input"))
      (node (ref "R15") (pin "2") (pinfunction "2_2") (pintype "passive"))
      (node (ref "U$1") (pin "D9") (pinfunction "D9_D9") (pintype "bidirectional"))
    )
    (net (code "24") (name "IN_B1") (class "Default")
      (node (ref "IC1") (pin "15") (pinfunction "4A_15") (pintype "input"))
      (node (ref "R13") (pin "1") (pinfunction "1_1") (pintype "passive"))
      (node (ref "U$1") (pin "D8") (pinfunction "D8_D8") (pintype "bidirectional"))
    )
    (net (code "25") (name "IN_B2") (class "Default")
      (node (ref "IC1") (pin "10") (pinfunction "3A_10") (pintype "input"))
      (node (ref "R12") (pin "1") (pinfunction "1_1") (pintype "passive"))
      (node (ref "U$1") (pin "D7") (pinfunction "D7_D7") (pintype "bidirectional"))
    )
    (net (code "26") (name "MISO") (class "Default")
      (node (ref "IC1") (pin "1") (pinfunction "1-2EN_1") (pintype "input"))
      (node (ref "JP1") (pin "1") (pinfunction "1_1") (pintype "passive"))
      (node (ref "U$1") (pin "D12") (pinfunction "D12_D12") (pintype "bidirectional"))
    )
    (net (code "27") (name "MOSI") (class "Default")
      (node (ref "IC1") (pin "9") (pinfunction "3-4EN_9") (pintype "input"))
      (node (ref "JP1") (pin "4") (pinfunction "4_4") (pintype "passive"))
      (node (ref "U$1") (pin "D11") (pinfunction "D11_D11") (pintype "bidirectional"))
    )
    (net (code "28") (name "MOT_A+") (class "Default")
      (node (ref "IC1") (pin "3") (pinfunction "1Y_3") (pintype "output"))
      (node (ref "MOT_A") (pin "2") (pinfunction "KL_2") (pintype "passive"))
    )
    (net (code "29") (name "MOT_A-") (class "Default")
      (node (ref "IC1") (pin "6") (pinfunction "2Y_6") (pintype "output"))
      (node (ref "MOT_A") (pin "1") (pinfunction "KL_1") (pintype "passive"))
    )
    (net (code "30") (name "MOT_B+") (class "Default")
      (node (ref "IC1") (pin "14") (pinfunction "4Y_14") (pintype "output"))
      (node (ref "MOT_B") (pin "2") (pinfunction "KL_2") (pintype "passive"))
    )
    (net (code "31") (name "MOT_B-") (class "Default")
      (node (ref "IC1") (pin "11") (pinfunction "3Y_11") (pintype "output"))
      (node (ref "MOT_B") (pin "1") (pinfunction "KL_1") (pintype "passive"))
    )
    (net (code "32") (name "Net-(C7-Pad2)") (class "Default")
      (node (ref "C7") (pin "2") (pinfunction "2_2") (pintype "passive"))
      (node (ref "Q1") (pin "1") (pinfunction "1_1") (pintype "passive"))
      (node (ref "U$1") (pin "CRYST1") (pinfunction "CRYST1_CRYST1") (pintype "bidirectional"))
    )
    (net (code "33") (name "Net-(C8-Pad2)") (class "Default")
      (node (ref "C8") (pin "2") (pinfunction "2_2") (pintype "passive"))
      (node (ref "Q1") (pin "3") (pinfunction "3_3") (pintype "passive"))
      (node (ref "U$1") (pin "CRYST2") (pinfunction "CRYST2_CRYST2") (pintype "bidirectional"))
    )
    (net (code "34") (name "Net-(IC1-VCC2)") (class "Default")
      (node (ref "IC1") (pin "8") (pinfunction "VCC2_8") (pintype "power_in"))
      (node (ref "U$5") (pin "ON") (pinfunction "ON_ON") (pintype "bidirectional"))
    )
    (net (code "35") (name "Net-(IC3-3V3OUT)") (class "Default")
      (node (ref "C2") (pin "1") (pinfunction "1_1") (pintype "passive"))
      (node (ref "IC3") (pin "17") (pinfunction "3V3OUT_17") (pintype "output"))
      (node (ref "IC3") (pin "4") (pinfunction "VCCIO_4") (pintype "power_in"))
      (node (ref "R24") (pin "1") (pinfunction "1_1") (pintype "passive"))
      (node (ref "R25") (pin "1") (pinfunction "1_1") (pintype "passive"))
    )
    (net (code "36") (name "Net-(IC3-CBUS0)") (class "Default")
      (node (ref "IC3") (pin "23") (pinfunction "CBUS0_23") (pintype "bidirectional"))
      (node (ref "TXD") (pin "C") (pinfunction "C_C") (pintype "passive"))
    )
    (net (code "37") (name "Net-(IC3-CBUS1)") (class "Default")
      (node (ref "IC3") (pin "22") (pinfunction "CBUS1_22") (pintype "bidirectional"))
      (node (ref "LED3") (pin "C") (pinfunction "C_C") (pintype "passive"))
    )
    (net (code "38") (name "Net-(IC3-RXD)") (class "Default")
      (node (ref "IC3") (pin "5") (pinfunction "RXD_5") (pintype "input"))
      (node (ref "SJ3") (pin "2") (pinfunction "2_2") (pintype "passive"))
    )
    (net (code "39") (name "Net-(IC3-TXD)") (class "Default")
      (node (ref "IC3") (pin "1") (pinfunction "TXD_1") (pintype "output"))
      (node (ref "SJ2") (pin "2") (pinfunction "2_2") (pintype "passive"))
    )
    (net (code "40") (name "Net-(IC3-_DTR)") (class "Default")
      (node (ref "C3") (pin "1") (pinfunction "1_1") (pintype "passive"))
      (node (ref "IC3") (pin "2") (pinfunction "_DTR_2") (pintype "input"))
    )
    (net (code "41") (name "Net-(IRFU9024-PadS)") (class "Default")
      (node (ref "IRFU9024") (pin "S") (pinfunction "S_S") (pintype "passive"))
      (node (ref "REVERSE") (pin "C") (pinfunction "C_C") (pintype "passive"))
      (node (ref "SJ1") (pin "2") (pinfunction "2_2") (pintype "passive"))
      (node (ref "U$7") (pin "+") (pinfunction "+_+") (pintype "power_in"))
      (node (ref "U$9") (pin "COM") (pinfunction "COM_COM") (pintype "bidirectional"))
    )
    (net (code "42") (name "Net-(LED1-PadC)") (class "Default")
      (node (ref "LED1") (pin "C") (pinfunction "C_C") (pintype "passive"))
      (node (ref "R5") (pin "1") (pinfunction "1_1") (pintype "passive"))
    )
    (net (code "43") (name "Net-(LED3-PadA)") (class "Default")
      (node (ref "LED3") (pin "A") (pinfunction "A_A") (pintype "passive"))
      (node (ref "R24") (pin "2") (pinfunction "2_2") (pintype "passive"))
    )
    (net (code "44") (name "Net-(LED5-DO)") (class "Default")
      (node (ref "LED5") (pin "2") (pinfunction "DO_2") (pintype "bidirectional"))
      (node (ref "LED6") (pin "4") (pinfunction "DI_4") (pintype "bidirectional"))
    )
    (net (code "45") (name "Net-(LED6-DO)") (class "Default")
      (node (ref "LED6") (pin "2") (pinfunction "DO_2") (pintype "bidirectional"))
      (node (ref "LED7") (pin "4") (pinfunction "DI_4") (pintype "bidirectional"))
    )
    (net (code "46") (name "Net-(LED7-DO)") (class "Default")
      (node (ref "LED7") (pin "2") (pinfunction "DO_2") (pintype "bidirectional"))
      (node (ref "LED8") (pin "4") (pinfunction "DI_4") (pintype "bidirectional"))
    )
    (net (code "47") (name "Net-(LS1-ANODE)") (class "Default")
      (node (ref "LS1") (pin "A") (pinfunction "ANODE_A") (pintype "passive"))
      (node (ref "R18") (pin "2") (pinfunction "2_2") (pintype "passive"))
    )
    (net (code "48") (name "Net-(LS1-COLLECTOR)") (class "Default")
      (node (ref "LS1") (pin "C") (pinfunction "COLLECTOR_C") (pintype "passive"))
      (node (ref "R19") (pin "2") (pinfunction "2_2") (pintype "passive"))
      (node (ref "U$13") (pin "LIGHTSENSOR") (pinfunction "LIGHTSENSOR_LIGHTSENSOR") (pintype "bidirectional"))
    )
    (net (code "49") (name "Net-(LS2-ANODE)") (class "Default")
      (node (ref "LS2") (pin "A") (pinfunction "ANODE_A") (pintype "passive"))
      (node (ref "R16") (pin "2") (pinfunction "2_2") (pintype "passive"))
    )
    (net (code "50") (name "Net-(LS2-COLLECTOR)") (class "Default")
      (node (ref "LS2") (pin "C") (pinfunction "COLLECTOR_C") (pintype "passive"))
      (node (ref "R17") (pin "2") (pinfunction "2_2") (pintype "passive"))
      (node (ref "U$14") (pin "LIGHTSENSOR") (pinfunction "LIGHTSENSOR_LIGHTSENSOR") (pintype "bidirectional"))
    )
    (net (code "51") (name "Net-(ON-PadA)") (class "Default")
      (node (ref "ON") (pin "A") (pinfunction "A_A") (pintype "passive"))
      (node (ref "R22") (pin "2") (pinfunction "2_2") (pintype "passive"))
    )
    (net (code "52") (name "Net-(R6-Pad2)") (class "Default")
      (node (ref "R6") (pin "2") (pinfunction "2_2") (pintype "passive"))
      (node (ref "REVERSE") (pin "A") (pinfunction "A_A") (pintype "passive"))
    )
    (net (code "53") (name "Net-(R8-Pad1)") (class "Default")
      (node (ref "R8") (pin "1") (pinfunction "1_1") (pintype "passive"))
      (node (ref "U$1") (pin "D1") (pinfunction "D1_D1") (pintype "bidirectional"))
    )
    (net (code "54") (name "Net-(R9-Pad1)") (class "Default")
      (node (ref "R9") (pin "1") (pinfunction "1_1") (pintype "passive"))
      (node (ref "U$1") (pin "D0") (pinfunction "D0_D0") (pintype "bidirectional"))
    )
    (net (code "55") (name "Net-(R11-Pad1)") (class "Default")
      (node (ref "R11") (pin "1") (pinfunction "1_1") (pintype "passive"))
      (node (ref "YELLOW") (pin "C") (pinfunction "C_C") (pintype "passive"))
    )
    (net (code "56") (name "Net-(R25-Pad2)") (class "Default")
      (node (ref "R25") (pin "2") (pinfunction "2_2") (pintype "passive"))
      (node (ref "TXD") (pin "A") (pinfunction "A_A") (pintype "passive"))
    )
    (net (code "57") (name "Net-(R26-Pad2)") (class "Default")
      (node (ref "R26") (pin "2") (pinfunction "2_2") (pintype "passive"))
      (node (ref "U$12") (pin "A1") (pinfunction "A1_A1") (pintype "bidirectional"))
    )
    (net (code "58") (name "Net-(R27-Pad2)") (class "Default")
      (node (ref "R27") (pin "2") (pinfunction "2_2") (pintype "passive"))
      (node (ref "U$13") (pin "COM") (pinfunction "COM_COM") (pintype "bidirectional"))
    )
    (net (code "59") (name "Net-(R28-Pad1)") (class "Default")
      (node (ref "R28") (pin "1") (pinfunction "1_1") (pintype "passive"))
      (node (ref "U$14") (pin "COM") (pinfunction "COM_COM") (pintype "bidirectional"))
    )
    (net (code "60") (name "Net-(TP4056-BAT)") (class "Default")
      (node (ref "C1") (pin "1") (pinfunction "1_1") (pintype "passive"))
      (node (ref "IRFU9024") (pin "D") (pinfunction "D_D") (pintype "passive"))
      (node (ref "SJ1") (pin "1") (pinfunction "1_1") (pintype "passive"))
      (node (ref "TP4056") (pin "5") (pinfunction "BAT_5") (pintype "bidirectional"))
      (node (ref "U$8") (pin "PWR@1") (pinfunction "+_PWR@1") (pintype "power_in"))
      (node (ref "U$8") (pin "PWR@2") (pinfunction "+1_PWR@2") (pintype "power_in"))
      (node (ref "U$8") (pin "PWR@3") (pinfunction "+2_PWR@3") (pintype "power_in"))
    )
    (net (code "61") (name "Net-(TP4056-CE)") (class "Default")
      (node (ref "LED1") (pin "A") (pinfunction "A_A") (pintype "passive"))
      (node (ref "R3") (pin "2") (pinfunction "2_2") (pintype "passive"))
      (node (ref "TP4056") (pin "4") (pinfunction "VCC_4") (pintype "bidirectional"))
      (node (ref "TP4056") (pin "8") (pinfunction "CE_8") (pintype "bidirectional"))
      (node (ref "YELLOW") (pin "A") (pinfunction "A_A") (pintype "passive"))
    )
    (net (code "62") (name "Net-(TP4056-CHRG)") (class "Default")
      (node (ref "R5") (pin "2") (pinfunction "2_2") (pintype "passive"))
      (node (ref "TP4056") (pin "7") (pinfunction "CHRG_7") (pintype "bidirectional"))
    )
    (net (code "63") (name "Net-(TP4056-PROG)") (class "Default")
      (node (ref "R4") (pin "1") (pinfunction "1_1") (pintype "passive"))
      (node (ref "TP4056") (pin "2") (pinfunction "PROG_2") (pintype "bidirectional"))
    )
    (net (code "64") (name "Net-(TP4056-STDBY)") (class "Default")
      (node (ref "R11") (pin "2") (pinfunction "2_2") (pintype "passive"))
      (node (ref "TP4056") (pin "6") (pinfunction "STDBY_6") (pintype "bidirectional"))
    )
    (net (code "65") (name "Net-(U$12-PadA2)") (class "Default")
      (node (ref "U$12") (pin "A2") (pinfunction "A2_A2") (pintype "bidirectional"))
      (node (ref "U$13") (pin "HEADER") (pinfunction "HEADER_HEADER") (pintype "bidirectional"))
    )
    (net (code "66") (name "Net-(U$12-PadA3)") (class "Default")
      (node (ref "U$12") (pin "A3") (pinfunction "A3_A3") (pintype "bidirectional"))
      (node (ref "U$14") (pin "HEADER") (pinfunction "HEADER_HEADER") (pintype "bidirectional"))
    )
    (net (code "67") (name "Net-(U1-D+)") (class "Default")
      (node (ref "SW1") (pin "COM2") (pinfunction "COM2_COM2") (pintype "bidirectional"))
      (node (ref "U1") (pin "D+1") (pinfunction "D+_D+1") (pintype "bidirectional"))
    )
    (net (code "68") (name "Net-(U1-D-)") (class "Default")
      (node (ref "SW1") (pin "COM1") (pinfunction "COM1_COM1") (pintype "bidirectional"))
      (node (ref "U1") (pin "D-1") (pinfunction "D-_D-1") (pintype "bidirectional"))
    )
    (net (code "69") (name "RESET") (class "Default")
      (node (ref "C3") (pin "2") (pinfunction "2_2") (pintype "passive"))
      (node (ref "JP1") (pin "5") (pinfunction "5_5") (pintype "passive"))
      (node (ref "R1") (pin "1") (pinfunction "1_1") (pintype "passive"))
      (node (ref "S2") (pin "2") (pinfunction "S1_2") (pintype "passive"))
      (node (ref "U$1") (pin "RESET") (pinfunction "RESET_RESET") (pintype "bidirectional"))
    )
    (net (code "70") (name "RXD") (class "Default")
      (node (ref "R9") (pin "2") (pinfunction "2_2") (pintype "passive"))
      (node (ref "SJ2") (pin "1") (pinfunction "1_1") (pintype "passive"))
      (node (ref "SJ3") (pin "3") (pinfunction "3_3") (pintype "passive"))
      (node (ref "U$2") (pin "D0") (pinfunction "D0_D0") (pintype "passive"))
      (node (ref "U$4") (pin "RXD") (pinfunction "RXD1_RXD") (pintype "bidirectional"))
      (node (ref "U$4") (pin "RXD2") (pinfunction "RXD2_RXD2") (pintype "bidirectional"))
    )
    (net (code "71") (name "SCK") (class "Default")
      (node (ref "JP1") (pin "3") (pinfunction "3_3") (pintype "passive"))
      (node (ref "LED5") (pin "4") (pinfunction "DI_4") (pintype "bidirectional"))
      (node (ref "R26") (pin "1") (pinfunction "1_1") (pintype "passive"))
      (node (ref "U$1") (pin "D13") (pinfunction "D13_D13") (pintype "bidirectional"))
    )
    (net (code "72") (name "SCL") (class "Default")
      (node (ref "R30") (pin "1") (pinfunction "1_1") (pintype "passive"))
      (node (ref "U$1") (pin "A5") (pinfunction "A5_A5") (pintype "bidirectional"))
      (node (ref "U$2") (pin "A5") (pinfunction "A5_A5") (pintype "passive"))
      (node (ref "U$3") (pin "SCL") (pinfunction "SCL_SCL") (pintype "bidirectional"))
      (node (ref "U$3") (pin "SCL2") (pinfunction "SCL2_SCL2") (pintype "bidirectional"))
      (node (ref "U2") (pin "5") (pinfunction "SCL_5") (pintype "input"))
      (node (ref "U3") (pin "SCL") (pinfunction "SCL_SCL") (pintype "bidirectional"))
    )
    (net (code "73") (name "SDA") (class "Default")
      (node (ref "R31") (pin "1") (pinfunction "1_1") (pintype "passive"))
      (node (ref "U$1") (pin "A4") (pinfunction "A4_A4") (pintype "bidirectional"))
      (node (ref "U$2") (pin "A4") (pinfunction "A4_A4") (pintype "passive"))
      (node (ref "U$3") (pin "SDA") (pinfunction "SDA_SDA") (pintype "bidirectional"))
      (node (ref "U$3") (pin "SDA2") (pinfunction "SDA2_SDA2") (pintype "bidirectional"))
      (node (ref "U2") (pin "6") (pinfunction "SDA_6") (pintype "bidirectional"))
      (node (ref "U3") (pin "SDA") (pinfunction "SDA_SDA") (pintype "bidirectional"))
    )
    (net (code "74") (name "TXD") (class "Default")
      (node (ref "R8") (pin "2") (pinfunction "2_2") (pintype "passive"))
      (node (ref "SJ2") (pin "3") (pinfunction "3_3") (pintype "passive"))
      (node (ref "SJ3") (pin "1") (pinfunction "1_1") (pintype "passive"))
      (node (ref "U$2") (pin "D1") (pinfunction "D1_D1") (pintype "passive"))
      (node (ref "U$4") (pin "TXD") (pinfunction "TXD_TXD") (pintype "bidirectional"))
      (node (ref "U$4") (pin "TXD2") (pinfunction "TXD2_TXD2") (pintype "bidirectional"))
    )
    (net (code "75") (name "VCC_MOT") (class "Default")
      (node (ref "U$21") (pin "OUT+") (pinfunction "OUT+_OUT+") (pintype "bidirectional"))
      (node (ref "U$5") (pin "COM") (pinfunction "COM_COM") (pintype "bidirectional"))
    )
    (net (code "76") (name "VUSB") (class "Default")
      (node (ref "IC3") (pin "20") (pinfunction "VCC_20") (pintype "power_in"))
      (node (ref "R3") (pin "1") (pinfunction "1_1") (pintype "passive"))
      (node (ref "U1") (pin "VBUS1") (pinfunction "VBUS_VBUS1") (pintype "bidirectional"))
    )
    (net (code "77") (name "unconnected-(IC3-CBUS2-Pad13)") (class "Default")
      (node (ref "IC3") (pin "13") (pinfunction "CBUS2_13") (pintype "bidirectional"))
    )
    (net (code "78") (name "unconnected-(IC3-CBUS3-Pad14)") (class "Default")
      (node (ref "IC3") (pin "14") (pinfunction "CBUS3_14") (pintype "bidirectional"))
    )
    (net (code "79") (name "unconnected-(IC3-CBUS4-Pad12)") (class "Default")
      (node (ref "IC3") (pin "12") (pinfunction "CBUS4_12") (pintype "bidirectional"))
    )
    (net (code "80") (name "unconnected-(IC3-NC-Pad8)") (class "Default")
      (node (ref "IC3") (pin "8") (pinfunction "NC_8") (pintype "no_connect"))
    )
    (net (code "81") (name "unconnected-(IC3-NC-Pad24)") (class "Default")
      (node (ref "IC3") (pin "24") (pinfunction "NC_24") (pintype "no_connect"))
    )
    (net (code "82") (name "unconnected-(IC3-OSCI-Pad27)") (class "Default")
      (node (ref "IC3") (pin "27") (pinfunction "OSCI_27") (pintype "input"))
    )
    (net (code "83") (name "unconnected-(IC3-OSCO-Pad28)") (class "Default")
      (node (ref "IC3") (pin "28") (pinfunction "OSCO_28") (pintype "output"))
    )
    (net (code "84") (name "unconnected-(IC3-_CTS-Pad11)") (class "Default")
      (node (ref "IC3") (pin "11") (pinfunction "_CTS_11") (pintype "input"))
    )
    (net (code "85") (name "unconnected-(IC3-_DCD-Pad10)") (class "Default")
      (node (ref "IC3") (pin "10") (pinfunction "_DCD_10") (pintype "input"))
    )
    (net (code "86") (name "unconnected-(IC3-_DSR-Pad9)") (class "Default")
      (node (ref "IC3") (pin "9") (pinfunction "_DSR_9") (pintype "input"))
    )
    (net (code "87") (name "unconnected-(IC3-_RESET-Pad19)") (class "Default")
      (node (ref "IC3") (pin "19") (pinfunction "_RESET_19") (pintype "input"))
    )
    (net (code "88") (name "unconnected-(IC3-_RI-Pad6)") (class "Default")
      (node (ref "IC3") (pin "6") (pinfunction "_RI_6") (pintype "input"))
    )
    (net (code "89") (name "unconnected-(IC3-_RTS-Pad3)") (class "Default")
      (node (ref "IC3") (pin "3") (pinfunction "_RTS_3") (pintype "output"))
    )
    (net (code "90") (name "unconnected-(JP1-Pad2)") (class "Default")
      (node (ref "JP1") (pin "2") (pinfunction "2_2") (pintype "passive"))
    )
    (net (code "91") (name "unconnected-(LED8-DO-Pad2)") (class "Default")
      (node (ref "LED8") (pin "2") (pinfunction "DO_2") (pintype "bidirectional"))
    )
    (net (code "92") (name "unconnected-(Q1-Pad2)") (class "Default")
      (node (ref "Q1") (pin "2") (pinfunction "2_2") (pintype "passive"))
    )
    (net (code "93") (name "unconnected-(S2-P-Pad3)") (class "Default")
      (node (ref "S2") (pin "3") (pinfunction "P_3") (pintype "passive"))
    )
    (net (code "94") (name "unconnected-(S2-S-Pad1)") (class "Default")
      (node (ref "S2") (pin "1") (pinfunction "S_1") (pintype "passive"))
    )
    (net (code "95") (name "unconnected-(S4-P-Pad3)") (class "Default")
      (node (ref "S4") (pin "3") (pinfunction "P_3") (pintype "passive"))
    )
    (net (code "96") (name "unconnected-(S4-S-Pad1)") (class "Default")
      (node (ref "S4") (pin "1") (pinfunction "S_1") (pintype "passive"))
    )
    (net (code "97") (name "unconnected-(U$1-Pad32)") (class "Default")
      (node (ref "U$1") (pin "32") (pinfunction "32_32") (pintype "bidirectional"))
    )
    (net (code "98") (name "unconnected-(U$1-PadAREF)") (class "Default")
      (node (ref "U$1") (pin "AREF") (pinfunction "AREF_AREF") (pintype "bidirectional"))
    )
    (net (code "99") (name "unconnected-(U$5-PadOFF)") (class "Default")
      (node (ref "U$5") (pin "OFF") (pinfunction "OFF_OFF") (pintype "bidirectional"))
    )
    (net (code "100") (name "unconnected-(U$9-PadOFF)") (class "Default")
      (node (ref "U$9") (pin "OFF") (pinfunction "OFF_OFF") (pintype "bidirectional"))
    )
    (net (code "101") (name "unconnected-(U1-USBID-PadID1)") (class "Default")
      (node (ref "U1") (pin "ID1") (pinfunction "USBID_ID1") (pintype "bidirectional"))
    )
    (net (code "102") (name "unconnected-(U3-PadADO)") (class "Default")
      (node (ref "U3") (pin "ADO") (pinfunction "ADO_ADO") (pintype "bidirectional"))
    )
    (net (code "103") (name "unconnected-(U3-PadINT)") (class "Default")
      (node (ref "U3") (pin "INT") (pinfunction "INT_INT") (pintype "bidirectional"))
    )
    (net (code "104") (name "unconnected-(U3-PadXCL)") (class "Default")
      (node (ref "U3") (pin "XCL") (pinfunction "XCL_XCL") (pintype "bidirectional"))
    )
    (net (code "105") (name "unconnected-(U3-PadXDA)") (class "Default")
      (node (ref "U3") (pin "XDA") (pinfunction "XDA_XDA") (pintype "bidirectional"))
    )
  )
)
